# CarPreamp.net
KiCad netlist of a schematic drawn in EAGLE
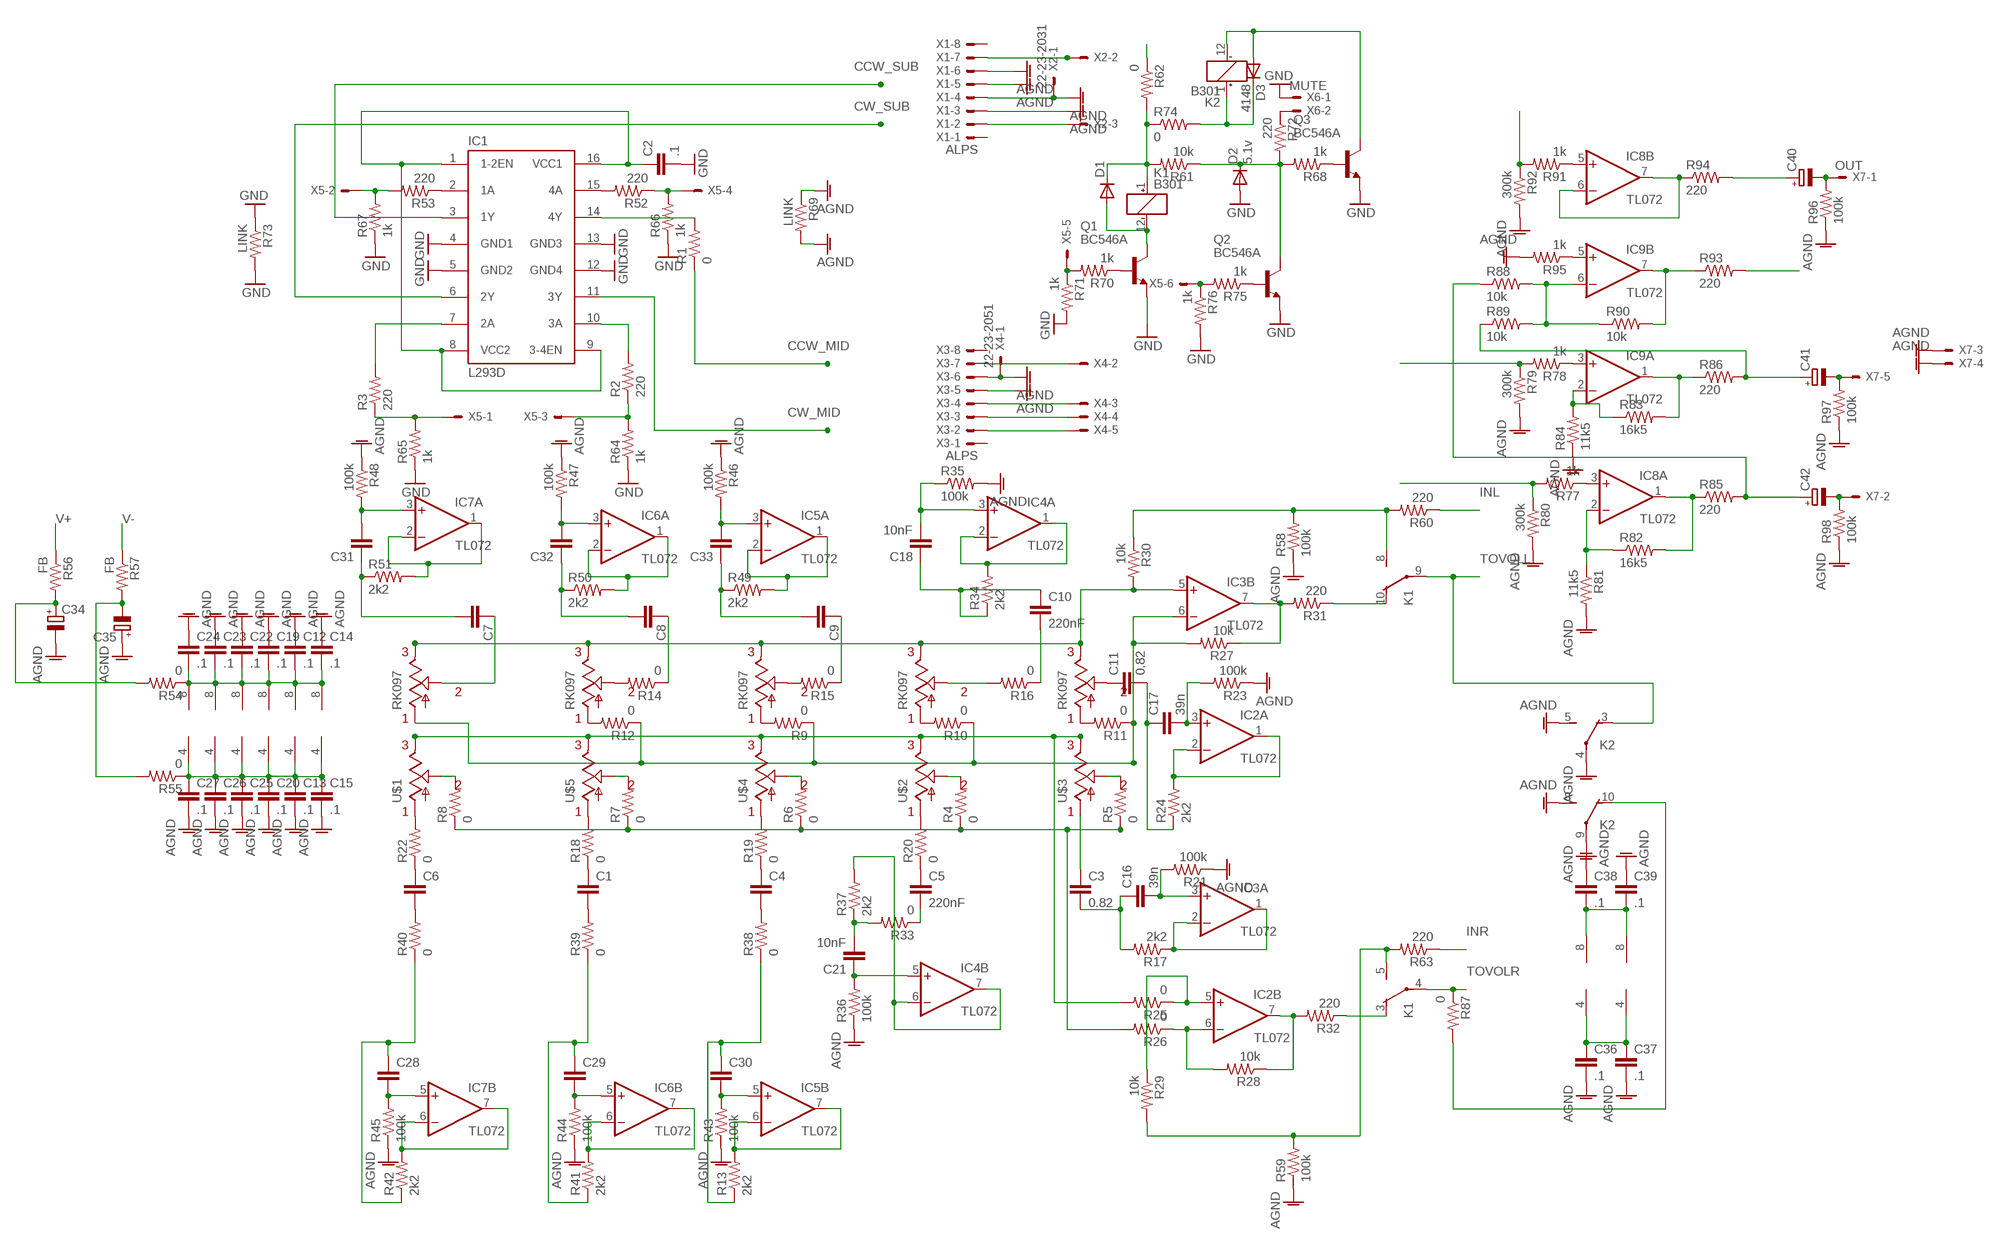
[diagram p0: schematic, sheet 1]

(export (version "E")
  (design (tool "Eeschema 10.0.6"))
  (components
    (comp (ref "C1")
      (value "C-EU050-035X075")
      (footprint "eagle-import:C050-035X075")
      (libsource (lib "eagle-import") (part "C-EU050-035X075"))
    )
    (comp (ref "C2")
      (value ".1")
      (footprint "eagle-import:C1210")
      (libsource (lib "eagle-import") (part "C-EUC1210"))
    )
    (comp (ref "C3")
      (value "0.82")
      (footprint "eagle-import:C075-032X103")
      (libsource (lib "eagle-import") (part "C-EU075-032X103"))
    )
    (comp (ref "C4")
      (value "C-EU050-035X075")
      (footprint "eagle-import:C050-035X075")
      (libsource (lib "eagle-import") (part "C-EU050-035X075"))
    )
    (comp (ref "C5")
      (value "220nF")
      (footprint "eagle-import:C050-035X075")
      (libsource (lib "eagle-import") (part "C-EU050-035X075"))
    )
    (comp (ref "C6")
      (value "C-EU050-035X075")
      (footprint "eagle-import:C050-035X075")
      (libsource (lib "eagle-import") (part "C-EU050-035X075"))
    )
    (comp (ref "C7")
      (value "C-EU050-035X075")
      (footprint "eagle-import:C050-035X075")
      (libsource (lib "eagle-import") (part "C-EU050-035X075"))
    )
    (comp (ref "C8")
      (value "C-EU050-035X075")
      (footprint "eagle-import:C050-035X075")
      (libsource (lib "eagle-import") (part "C-EU050-035X075"))
    )
    (comp (ref "C9")
      (value "C-EU050-035X075")
      (footprint "eagle-import:C050-035X075")
      (libsource (lib "eagle-import") (part "C-EU050-035X075"))
    )
    (comp (ref "C10")
      (value "220nF")
      (footprint "eagle-import:C050-035X075")
      (libsource (lib "eagle-import") (part "C-EU050-035X075"))
    )
    (comp (ref "C11")
      (value "0.82")
      (footprint "eagle-import:C075-032X103")
      (libsource (lib "eagle-import") (part "C-EU075-032X103"))
    )
    (comp (ref "C12")
      (value ".1")
      (footprint "eagle-import:C1210")
      (libsource (lib "eagle-import") (part "C-EUC1210"))
    )
    (comp (ref "C13")
      (value ".1")
      (footprint "eagle-import:C1210")
      (libsource (lib "eagle-import") (part "C-EUC1210"))
    )
    (comp (ref "C14")
      (value ".1")
      (footprint "eagle-import:C1210")
      (libsource (lib "eagle-import") (part "C-EUC1210"))
    )
    (comp (ref "C15")
      (value ".1")
      (footprint "eagle-import:C1210")
      (libsource (lib "eagle-import") (part "C-EUC1210"))
    )
    (comp (ref "C16")
      (value "39n")
      (footprint "eagle-import:C050-035X075")
      (libsource (lib "eagle-import") (part "C-EU050-035X075"))
    )
    (comp (ref "C17")
      (value "39n")
      (footprint "eagle-import:C050-035X075")
      (libsource (lib "eagle-import") (part "C-EU050-035X075"))
    )
    (comp (ref "C18")
      (value "10nF")
      (footprint "eagle-import:C050-035X075")
      (libsource (lib "eagle-import") (part "C-EU050-035X075"))
    )
    (comp (ref "C19")
      (value ".1")
      (footprint "eagle-import:C1210")
      (libsource (lib "eagle-import") (part "C-EUC1210"))
    )
    (comp (ref "C20")
      (value ".1")
      (footprint "eagle-import:C1210")
      (libsource (lib "eagle-import") (part "C-EUC1210"))
    )
    (comp (ref "C21")
      (value "10nF")
      (footprint "eagle-import:C050-035X075")
      (libsource (lib "eagle-import") (part "C-EU050-035X075"))
    )
    (comp (ref "C22")
      (value ".1")
      (footprint "eagle-import:C1210")
      (libsource (lib "eagle-import") (part "C-EUC1210"))
    )
    (comp (ref "C23")
      (value ".1")
      (footprint "eagle-import:C1210")
      (libsource (lib "eagle-import") (part "C-EUC1210"))
    )
    (comp (ref "C24")
      (value ".1")
      (footprint "eagle-import:C1210")
      (libsource (lib "eagle-import") (part "C-EUC1210"))
    )
    (comp (ref "C25")
      (value ".1")
      (footprint "eagle-import:C1210")
      (libsource (lib "eagle-import") (part "C-EUC1210"))
    )
    (comp (ref "C26")
      (value ".1")
      (footprint "eagle-import:C1210")
      (libsource (lib "eagle-import") (part "C-EUC1210"))
    )
    (comp (ref "C27")
      (value ".1")
      (footprint "eagle-import:C1210")
      (libsource (lib "eagle-import") (part "C-EUC1210"))
    )
    (comp (ref "C28")
      (value "C-EU050-035X075")
      (footprint "eagle-import:C050-035X075")
      (libsource (lib "eagle-import") (part "C-EU050-035X075"))
    )
    (comp (ref "C29")
      (value "C-EU050-035X075")
      (footprint "eagle-import:C050-035X075")
      (libsource (lib "eagle-import") (part "C-EU050-035X075"))
    )
    (comp (ref "C30")
      (value "C-EU050-035X075")
      (footprint "eagle-import:C050-035X075")
      (libsource (lib "eagle-import") (part "C-EU050-035X075"))
    )
    (comp (ref "C31")
      (value "C-EU050-035X075")
      (footprint "eagle-import:C050-035X075")
      (libsource (lib "eagle-import") (part "C-EU050-035X075"))
    )
    (comp (ref "C32")
      (value "C-EU050-035X075")
      (footprint "eagle-import:C050-035X075")
      (libsource (lib "eagle-import") (part "C-EU050-035X075"))
    )
    (comp (ref "C33")
      (value "C-EU050-035X075")
      (footprint "eagle-import:C050-035X075")
      (libsource (lib "eagle-import") (part "C-EU050-035X075"))
    )
    (comp (ref "C34")
      (value "CPOL-EUE3.5-8")
      (footprint "eagle-import:E3,5-8")
      (libsource (lib "eagle-import") (part "CPOL-EUE3.5-8"))
    )
    (comp (ref "C35")
      (value "CPOL-EUE3.5-8")
      (footprint "eagle-import:E3,5-8")
      (libsource (lib "eagle-import") (part "CPOL-EUE3.5-8"))
    )
    (comp (ref "C36")
      (value ".1")
      (footprint "eagle-import:C1210")
      (libsource (lib "eagle-import") (part "C-EUC1210"))
    )
    (comp (ref "C37")
      (value ".1")
      (footprint "eagle-import:C1210")
      (libsource (lib "eagle-import") (part "C-EUC1210"))
    )
    (comp (ref "C38")
      (value ".1")
      (footprint "eagle-import:C1210")
      (libsource (lib "eagle-import") (part "C-EUC1210"))
    )
    (comp (ref "C39")
      (value ".1")
      (footprint "eagle-import:C1210")
      (libsource (lib "eagle-import") (part "C-EUC1210"))
    )
    (comp (ref "C40")
      (value "CPOL-EUE3.5-8")
      (footprint "eagle-import:E3,5-8")
      (libsource (lib "eagle-import") (part "CPOL-EUE3.5-8"))
    )
    (comp (ref "C41")
      (value "CPOL-EUE3.5-8")
      (footprint "eagle-import:E3,5-8")
      (libsource (lib "eagle-import") (part "CPOL-EUE3.5-8"))
    )
    (comp (ref "C42")
      (value "CPOL-EUE3.5-8")
      (footprint "eagle-import:E3,5-8")
      (libsource (lib "eagle-import") (part "CPOL-EUE3.5-8"))
    )
    (comp (ref "D1")
      (value "1N4148DO35-10")
      (footprint "eagle-import:DO35-10")
      (libsource (lib "eagle-import") (part "1N4148DO35-10"))
    )
    (comp (ref "D2")
      (value "5.1v")
      (footprint "eagle-import:DO35-10")
      (libsource (lib "eagle-import") (part "1N4148DO35-10"))
    )
    (comp (ref "D3")
      (value "4148")
      (footprint "eagle-import:DO35-10")
      (libsource (lib "eagle-import") (part "1N4148DO35-10"))
    )
    (comp (ref "IC1")
      (value "L293D")
      (footprint "eagle-import:DIL16")
      (libsource (lib "eagle-import") (part "L293D"))
    )
    (comp (ref "IC2")
      (value "TL072")
      (footprint "eagle-import:DIL08")
      (libsource (lib "eagle-import") (part "1458NLM"))
    )
    (comp (ref "IC3")
      (value "TL072")
      (footprint "eagle-import:DIL08")
      (libsource (lib "eagle-import") (part "1458NLM"))
    )
    (comp (ref "IC4")
      (value "TL072")
      (footprint "eagle-import:DIL08")
      (libsource (lib "eagle-import") (part "1458NLM"))
    )
    (comp (ref "IC5")
      (value "TL072")
      (footprint "eagle-import:DIL08")
      (libsource (lib "eagle-import") (part "1458NLM"))
    )
    (comp (ref "IC6")
      (value "TL072")
      (footprint "eagle-import:DIL08")
      (libsource (lib "eagle-import") (part "1458NLM"))
    )
    (comp (ref "IC7")
      (value "TL072")
      (footprint "eagle-import:DIL08")
      (libsource (lib "eagle-import") (part "1458NLM"))
    )
    (comp (ref "IC8")
      (value "TL072")
      (footprint "eagle-import:DIL08")
      (libsource (lib "eagle-import") (part "1458NLM"))
    )
    (comp (ref "IC9")
      (value "TL072")
      (footprint "eagle-import:DIL08")
      (libsource (lib "eagle-import") (part "1458NLM"))
    )
    (comp (ref "K1")
      (value "B301")
      (footprint "eagle-import:TXD2")
      (libsource (lib "eagle-import") (part "TX?-D26V"))
    )
    (comp (ref "K2")
      (value "B301")
      (footprint "eagle-import:TXD2")
      (libsource (lib "eagle-import") (part "TX?-D26V"))
    )
    (comp (ref "Q1")
      (value "BC546A")
      (footprint "eagle-import:TO92-EBC")
      (libsource (lib "eagle-import") (part "BC546A"))
    )
    (comp (ref "Q2")
      (value "BC546A")
      (footprint "eagle-import:TO92-EBC")
      (libsource (lib "eagle-import") (part "BC546A"))
    )
    (comp (ref "Q3")
      (value "BC546A")
      (footprint "eagle-import:TO92-EBC")
      (libsource (lib "eagle-import") (part "BC546A"))
    )
    (comp (ref "R1")
      (value "0")
      (footprint "eagle-import:0309_12")
      (libsource (lib "eagle-import") (part "R-US_0309/12"))
    )
    (comp (ref "R2")
      (value "220")
      (footprint "eagle-import:0309_12")
      (libsource (lib "eagle-import") (part "R-US_0309/12"))
    )
    (comp (ref "R3")
      (value "220")
      (footprint "eagle-import:0207_15")
      (libsource (lib "eagle-import") (part "R-US_0207/15"))
    )
    (comp (ref "R4")
      (value "0")
      (footprint "eagle-import:0207_7")
      (libsource (lib "eagle-import") (part "R-US_0207/7"))
    )
    (comp (ref "R5")
      (value "0")
      (footprint "eagle-import:0207_7")
      (libsource (lib "eagle-import") (part "R-US_0207/7"))
    )
    (comp (ref "R6")
      (value "0")
      (footprint "eagle-import:0207_7")
      (libsource (lib "eagle-import") (part "R-US_0207/7"))
    )
    (comp (ref "R7")
      (value "0")
      (footprint "eagle-import:0207_7")
      (libsource (lib "eagle-import") (part "R-US_0207/7"))
    )
    (comp (ref "R8")
      (value "0")
      (footprint "eagle-import:0207_7")
      (libsource (lib "eagle-import") (part "R-US_0207/7"))
    )
    (comp (ref "R9")
      (value "0")
      (footprint "eagle-import:0207_7")
      (libsource (lib "eagle-import") (part "R-US_0207/7"))
    )
    (comp (ref "R10")
      (value "0")
      (footprint "eagle-import:0207_7")
      (libsource (lib "eagle-import") (part "R-US_0207/7"))
    )
    (comp (ref "R11")
      (value "0")
      (footprint "eagle-import:0207_7")
      (libsource (lib "eagle-import") (part "R-US_0207/7"))
    )
    (comp (ref "R12")
      (value "0")
      (footprint "eagle-import:0207_7")
      (libsource (lib "eagle-import") (part "R-US_0207/7"))
    )
    (comp (ref "R13")
      (value "2k2")
      (footprint "eagle-import:0207_7")
      (libsource (lib "eagle-import") (part "R-US_0207/7"))
    )
    (comp (ref "R14")
      (value "0")
      (footprint "eagle-import:0207_7")
      (libsource (lib "eagle-import") (part "R-US_0207/7"))
    )
    (comp (ref "R15")
      (value "0")
      (footprint "eagle-import:0207_7")
      (libsource (lib "eagle-import") (part "R-US_0207/7"))
    )
    (comp (ref "R16")
      (value "0")
      (footprint "eagle-import:0207_7")
      (libsource (lib "eagle-import") (part "R-US_0207/7"))
    )
    (comp (ref "R17")
      (value "2k2")
      (footprint "eagle-import:0207_7")
      (libsource (lib "eagle-import") (part "R-US_0207/7"))
    )
    (comp (ref "R18")
      (value "0")
      (footprint "eagle-import:0207_7")
      (libsource (lib "eagle-import") (part "R-US_0207/7"))
    )
    (comp (ref "R19")
      (value "0")
      (footprint "eagle-import:0207_7")
      (libsource (lib "eagle-import") (part "R-US_0207/7"))
    )
    (comp (ref "R20")
      (value "0")
      (footprint "eagle-import:0207_7")
      (libsource (lib "eagle-import") (part "R-US_0207/7"))
    )
    (comp (ref "R21")
      (value "100k")
      (footprint "eagle-import:0207_7")
      (libsource (lib "eagle-import") (part "R-US_0207/7"))
    )
    (comp (ref "R22")
      (value "0")
      (footprint "eagle-import:0207_7")
      (libsource (lib "eagle-import") (part "R-US_0207/7"))
    )
    (comp (ref "R23")
      (value "100k")
      (footprint "eagle-import:0207_7")
      (libsource (lib "eagle-import") (part "R-US_0207/7"))
    )
    (comp (ref "R24")
      (value "2k2")
      (footprint "eagle-import:0207_7")
      (libsource (lib "eagle-import") (part "R-US_0207/7"))
    )
    (comp (ref "R25")
      (value "0")
      (footprint "eagle-import:0207_10")
      (libsource (lib "eagle-import") (part "R-US_0207/10"))
    )
    (comp (ref "R26")
      (value "0")
      (footprint "eagle-import:0207_12")
      (libsource (lib "eagle-import") (part "R-US_0207/12"))
    )
    (comp (ref "R27")
      (value "10k")
      (footprint "eagle-import:R1210")
      (libsource (lib "eagle-import") (part "R-US_R1210"))
    )
    (comp (ref "R28")
      (value "10k")
      (footprint "eagle-import:R1210")
      (libsource (lib "eagle-import") (part "R-US_R1210"))
    )
    (comp (ref "R29")
      (value "10k")
      (footprint "eagle-import:0207_7")
      (libsource (lib "eagle-import") (part "R-US_0207/7"))
    )
    (comp (ref "R30")
      (value "10k")
      (footprint "eagle-import:0207_12")
      (libsource (lib "eagle-import") (part "R-US_0207/12"))
    )
    (comp (ref "R31")
      (value "220")
      (footprint "eagle-import:0207_7")
      (libsource (lib "eagle-import") (part "R-US_0207/7"))
    )
    (comp (ref "R32")
      (value "220")
      (footprint "eagle-import:0207_12")
      (libsource (lib "eagle-import") (part "R-US_0207/12"))
    )
    (comp (ref "R33")
      (value "0")
      (footprint "eagle-import:0309_10")
      (libsource (lib "eagle-import") (part "R-US_0309/10"))
    )
    (comp (ref "R34")
      (value "2k2")
      (footprint "eagle-import:0207_7")
      (libsource (lib "eagle-import") (part "R-US_0207/7"))
    )
    (comp (ref "R35")
      (value "100k")
      (footprint "eagle-import:0207_7")
      (libsource (lib "eagle-import") (part "R-US_0207/7"))
    )
    (comp (ref "R36")
      (value "100k")
      (footprint "eagle-import:0207_7")
      (libsource (lib "eagle-import") (part "R-US_0207/7"))
    )
    (comp (ref "R37")
      (value "2k2")
      (footprint "eagle-import:0207_7")
      (libsource (lib "eagle-import") (part "R-US_0207/7"))
    )
    (comp (ref "R38")
      (value "0")
      (footprint "eagle-import:0207_10")
      (libsource (lib "eagle-import") (part "R-US_0207/10"))
    )
    (comp (ref "R39")
      (value "0")
      (footprint "eagle-import:0207_10")
      (libsource (lib "eagle-import") (part "R-US_0207/10"))
    )
    (comp (ref "R40")
      (value "0")
      (footprint "eagle-import:0207_10")
      (libsource (lib "eagle-import") (part "R-US_0207/10"))
    )
    (comp (ref "R41")
      (value "2k2")
      (footprint "eagle-import:0207_7")
      (libsource (lib "eagle-import") (part "R-US_0207/7"))
    )
    (comp (ref "R42")
      (value "2k2")
      (footprint "eagle-import:0207_7")
      (libsource (lib "eagle-import") (part "R-US_0207/7"))
    )
    (comp (ref "R43")
      (value "100k")
      (footprint "eagle-import:0207_7")
      (libsource (lib "eagle-import") (part "R-US_0207/7"))
    )
    (comp (ref "R44")
      (value "100k")
      (footprint "eagle-import:0207_7")
      (libsource (lib "eagle-import") (part "R-US_0207/7"))
    )
    (comp (ref "R45")
      (value "100k")
      (footprint "eagle-import:0207_7")
      (libsource (lib "eagle-import") (part "R-US_0207/7"))
    )
    (comp (ref "R46")
      (value "100k")
      (footprint "eagle-import:0207_7")
      (libsource (lib "eagle-import") (part "R-US_0207/7"))
    )
    (comp (ref "R47")
      (value "100k")
      (footprint "eagle-import:0207_7")
      (libsource (lib "eagle-import") (part "R-US_0207/7"))
    )
    (comp (ref "R48")
      (value "100k")
      (footprint "eagle-import:0207_7")
      (libsource (lib "eagle-import") (part "R-US_0207/7"))
    )
    (comp (ref "R49")
      (value "2k2")
      (footprint "eagle-import:0207_7")
      (libsource (lib "eagle-import") (part "R-US_0207/7"))
    )
    (comp (ref "R50")
      (value "2k2")
      (footprint "eagle-import:0207_7")
      (libsource (lib "eagle-import") (part "R-US_0207/7"))
    )
    (comp (ref "R51")
      (value "2k2")
      (footprint "eagle-import:0207_7")
      (libsource (lib "eagle-import") (part "R-US_0207/7"))
    )
    (comp (ref "R52")
      (value "220")
      (footprint "eagle-import:0309_10")
      (libsource (lib "eagle-import") (part "R-US_0309/10"))
    )
    (comp (ref "R53")
      (value "220")
      (footprint "eagle-import:0309_10")
      (libsource (lib "eagle-import") (part "R-US_0309/10"))
    )
    (comp (ref "R54")
      (value "0")
      (footprint "eagle-import:0309_10")
      (libsource (lib "eagle-import") (part "R-US_0309/10"))
    )
    (comp (ref "R55")
      (value "0")
      (footprint "eagle-import:0411_15")
      (libsource (lib "eagle-import") (part "R-US_0411/15"))
    )
    (comp (ref "R56")
      (value "FB")
      (footprint "eagle-import:0309_12")
      (libsource (lib "eagle-import") (part "R-US_0309/12"))
    )
    (comp (ref "R57")
      (value "FB")
      (footprint "eagle-import:0309_12")
      (libsource (lib "eagle-import") (part "R-US_0309/12"))
    )
    (comp (ref "R58")
      (value "100k")
      (footprint "eagle-import:0207_7")
      (libsource (lib "eagle-import") (part "R-US_0207/7"))
    )
    (comp (ref "R59")
      (value "100k")
      (footprint "eagle-import:0207_7")
      (libsource (lib "eagle-import") (part "R-US_0207/7"))
    )
    (comp (ref "R60")
      (value "220")
      (footprint "eagle-import:0207_7")
      (libsource (lib "eagle-import") (part "R-US_0207/7"))
    )
    (comp (ref "R61")
      (value "10k")
      (footprint "eagle-import:R1210")
      (libsource (lib "eagle-import") (part "R-US_R1210"))
    )
    (comp (ref "R62")
      (value "0")
      (footprint "eagle-import:0309_10")
      (libsource (lib "eagle-import") (part "R-US_0309/10"))
    )
    (comp (ref "R63")
      (value "220")
      (footprint "eagle-import:0207_7")
      (libsource (lib "eagle-import") (part "R-US_0207/7"))
    )
    (comp (ref "R64")
      (value "1k")
      (footprint "eagle-import:R1210")
      (libsource (lib "eagle-import") (part "R-US_R1210"))
    )
    (comp (ref "R65")
      (value "1k")
      (footprint "eagle-import:R1210")
      (libsource (lib "eagle-import") (part "R-US_R1210"))
    )
    (comp (ref "R66")
      (value "1k")
      (footprint "eagle-import:R1210")
      (libsource (lib "eagle-import") (part "R-US_R1210"))
    )
    (comp (ref "R67")
      (value "1k")
      (footprint "eagle-import:R1210")
      (libsource (lib "eagle-import") (part "R-US_R1210"))
    )
    (comp (ref "R68")
      (value "1k")
      (footprint "eagle-import:R1210")
      (libsource (lib "eagle-import") (part "R-US_R1210"))
    )
    (comp (ref "R69")
      (value "LINK")
      (footprint "eagle-import:0309_12")
      (libsource (lib "eagle-import") (part "R-US_0309/12"))
    )
    (comp (ref "R70")
      (value "1k")
      (footprint "eagle-import:R1210")
      (libsource (lib "eagle-import") (part "R-US_R1210"))
    )
    (comp (ref "R71")
      (value "1k")
      (footprint "eagle-import:R1210")
      (libsource (lib "eagle-import") (part "R-US_R1210"))
    )
    (comp (ref "R72")
      (value "220")
      (footprint "eagle-import:R1210")
      (libsource (lib "eagle-import") (part "R-US_R1210"))
    )
    (comp (ref "R73")
      (value "LINK")
      (footprint "eagle-import:0309_10")
      (libsource (lib "eagle-import") (part "R-US_0309/10"))
    )
    (comp (ref "R74")
      (value "0")
      (footprint "eagle-import:0309_12")
      (libsource (lib "eagle-import") (part "R-US_0309/12"))
    )
    (comp (ref "R75")
      (value "1k")
      (footprint "eagle-import:0309_10")
      (libsource (lib "eagle-import") (part "R-US_0309/10"))
    )
    (comp (ref "R76")
      (value "1k")
      (footprint "eagle-import:0309_10")
      (libsource (lib "eagle-import") (part "R-US_0309/10"))
    )
    (comp (ref "R77")
      (value "1k")
      (footprint "eagle-import:0207_7")
      (libsource (lib "eagle-import") (part "R-US_0207/7"))
    )
    (comp (ref "R78")
      (value "1k")
      (footprint "eagle-import:0207_7")
      (libsource (lib "eagle-import") (part "R-US_0207/7"))
    )
    (comp (ref "R79")
      (value "300k")
      (footprint "eagle-import:0207_7")
      (libsource (lib "eagle-import") (part "R-US_0207/7"))
    )
    (comp (ref "R80")
      (value "300k")
      (footprint "eagle-import:0207_7")
      (libsource (lib "eagle-import") (part "R-US_0207/7"))
    )
    (comp (ref "R81")
      (value "11k5")
      (footprint "eagle-import:0207_7")
      (libsource (lib "eagle-import") (part "R-US_0207/7"))
    )
    (comp (ref "R82")
      (value "16k5")
      (footprint "eagle-import:0207_7")
      (libsource (lib "eagle-import") (part "R-US_0207/7"))
    )
    (comp (ref "R83")
      (value "16k5")
      (footprint "eagle-import:0207_7")
      (libsource (lib "eagle-import") (part "R-US_0207/7"))
    )
    (comp (ref "R84")
      (value "11k5")
      (footprint "eagle-import:0207_7")
      (libsource (lib "eagle-import") (part "R-US_0207/7"))
    )
    (comp (ref "R85")
      (value "220")
      (footprint "eagle-import:0207_7")
      (libsource (lib "eagle-import") (part "R-US_0207/7"))
    )
    (comp (ref "R86")
      (value "220")
      (footprint "eagle-import:0207_7")
      (libsource (lib "eagle-import") (part "R-US_0207/7"))
    )
    (comp (ref "R87")
      (value "0")
      (footprint "eagle-import:0207_10")
      (libsource (lib "eagle-import") (part "R-US_0207/10"))
    )
    (comp (ref "R88")
      (value "10k")
      (footprint "eagle-import:0207_7")
      (libsource (lib "eagle-import") (part "R-US_0207/7"))
    )
    (comp (ref "R89")
      (value "10k")
      (footprint "eagle-import:0207_7")
      (libsource (lib "eagle-import") (part "R-US_0207/7"))
    )
    (comp (ref "R90")
      (value "10k")
      (footprint "eagle-import:0207_7")
      (libsource (lib "eagle-import") (part "R-US_0207/7"))
    )
    (comp (ref "R91")
      (value "1k")
      (footprint "eagle-import:0207_7")
      (libsource (lib "eagle-import") (part "R-US_0207/7"))
    )
    (comp (ref "R92")
      (value "300k")
      (footprint "eagle-import:0207_7")
      (libsource (lib "eagle-import") (part "R-US_0207/7"))
    )
    (comp (ref "R93")
      (value "220")
      (footprint "eagle-import:0207_7")
      (libsource (lib "eagle-import") (part "R-US_0207/7"))
    )
    (comp (ref "R94")
      (value "220")
      (footprint "eagle-import:0207_7")
      (libsource (lib "eagle-import") (part "R-US_0207/7"))
    )
    (comp (ref "R95")
      (value "1k")
      (footprint "eagle-import:0207_10")
      (libsource (lib "eagle-import") (part "R-US_0207/10"))
    )
    (comp (ref "R96")
      (value "100k")
      (footprint "eagle-import:0207_7")
      (libsource (lib "eagle-import") (part "R-US_0207/7"))
    )
    (comp (ref "R97")
      (value "100k")
      (footprint "eagle-import:0207_7")
      (libsource (lib "eagle-import") (part "R-US_0207/7"))
    )
    (comp (ref "R98")
      (value "100k")
      (footprint "eagle-import:0207_7")
      (libsource (lib "eagle-import") (part "R-US_0207/7"))
    )
    (comp (ref "U$1")
      (value "RK097")
      (footprint "eagle-import:RK097-DUAL-ELEMENT")
      (libsource (lib "eagle-import") (part "RK097-DUAL-ELEMENT"))
    )
    (comp (ref "U$2")
      (value "RK097")
      (footprint "eagle-import:RK097-DUAL-ELEMENT")
      (libsource (lib "eagle-import") (part "RK097-DUAL-ELEMENT"))
    )
    (comp (ref "U$3")
      (value "RK097")
      (footprint "eagle-import:RK097-DUAL-ELEMENT")
      (libsource (lib "eagle-import") (part "RK097-DUAL-ELEMENT"))
    )
    (comp (ref "U$4")
      (value "RK097")
      (footprint "eagle-import:RK097-DUAL-ELEMENT")
      (libsource (lib "eagle-import") (part "RK097-DUAL-ELEMENT"))
    )
    (comp (ref "U$5")
      (value "RK097")
      (footprint "eagle-import:RK097-DUAL-ELEMENT")
      (libsource (lib "eagle-import") (part "RK097-DUAL-ELEMENT"))
    )
    (comp (ref "X1")
      (value "ALPS")
      (footprint "eagle-import:22-23-2081")
      (fields (field (name "MF") "MOLEX") (field (name "MPN") "22-23-2081"))
      (libsource (lib "eagle-import") (part "22-23-2081"))
    )
    (comp (ref "X2")
      (value "22-23-2031")
      (footprint "eagle-import:22-23-2031")
      (fields (field (name "MF") "MOLEX"))
      (libsource (lib "eagle-import") (part "22-23-2031"))
    )
    (comp (ref "X3")
      (value "ALPS")
      (footprint "eagle-import:22-23-2081")
      (fields (field (name "MF") "MOLEX") (field (name "MPN") "22-23-2081"))
      (libsource (lib "eagle-import") (part "22-23-2081"))
    )
    (comp (ref "X4")
      (value "22-23-2051")
      (footprint "eagle-import:22-23-2051")
      (fields (field (name "MF") "MOLEX"))
      (libsource (lib "eagle-import") (part "22-23-2051"))
    )
    (comp (ref "X5")
      (value "22-23-2061")
      (footprint "eagle-import:22-23-2061")
      (fields (field (name "MF") "MOLEX"))
      (libsource (lib "eagle-import") (part "22-23-2061"))
    )
    (comp (ref "X6")
      (value "MUTE")
      (footprint "eagle-import:22-23-2021")
      (fields (field (name "MF") "MOLEX") (field (name "MPN") "22-23-2021"))
      (libsource (lib "eagle-import") (part "22-23-2021"))
    )
    (comp (ref "X7")
      (value "OUT")
      (footprint "eagle-import:22-23-2051")
      (fields (field (name "MF") "MOLEX") (field (name "MPN") "22-23-2051"))
      (libsource (lib "eagle-import") (part "22-23-2051"))
    )
  )
  (nets
    (net (code "1") (name "/5V") (class "Default")
      (node (ref "C2") (pin "1") (pinfunction "1_1") (pintype "passive"))
      (node (ref "IC1") (pin "1") (pinfunction "1-2EN_1") (pintype "input"))
      (node (ref "IC1") (pin "16") (pinfunction "VCC1_16") (pintype "power_in"))
      (node (ref "IC1") (pin "8") (pinfunction "VCC2_8") (pintype "power_in"))
      (node (ref "IC1") (pin "9") (pinfunction "3-4EN_9") (pintype "input"))
      (node (ref "R62") (pin "1") (pinfunction "1_1") (pintype "passive"))
    )
    (net (code "2") (name "/CCW_MID") (class "Default")
      (node (ref "R1") (pin "1") (pinfunction "1_1") (pintype "passive"))
    )
    (net (code "3") (name "/CCW_SUB") (class "Default")
      (node (ref "IC1") (pin "3") (pinfunction "1Y_3") (pintype "output"))
    )
    (net (code "4") (name "/CW_MID") (class "Default")
      (node (ref "IC1") (pin "11") (pinfunction "3Y_11") (pintype "output"))
    )
    (net (code "5") (name "/CW_SUB") (class "Default")
      (node (ref "IC1") (pin "6") (pinfunction "2Y_6") (pintype "output"))
    )
    (net (code "6") (name "/INL") (class "Default")
      (node (ref "R60") (pin "1") (pinfunction "1_1") (pintype "passive"))
    )
    (net (code "7") (name "/INR") (class "Default")
      (node (ref "R63") (pin "1") (pinfunction "1_1") (pintype "passive"))
    )
    (net (code "8") (name "/TOVOLL") (class "Default")
      (node (ref "K1") (pin "9") (pinfunction "P_9") (pintype "passive"))
      (node (ref "K2") (pin "3") (pinfunction "O_3") (pintype "passive"))
    )
    (net (code "9") (name "/TOVOLR") (class "Default")
      (node (ref "K1") (pin "4") (pinfunction "P_4") (pintype "passive"))
      (node (ref "R87") (pin "1") (pinfunction "1_1") (pintype "passive"))
    )
    (net (code "10") (name "/V+") (class "Default")
      (node (ref "R56") (pin "1") (pinfunction "1_1") (pintype "passive"))
    )
    (net (code "11") (name "/V-") (class "Default")
      (node (ref "R57") (pin "1") (pinfunction "1_1") (pintype "passive"))
    )
    (net (code "12") (name "AGND") (class "Default")
      (node (ref "C12") (pin "1") (pinfunction "1_1") (pintype "passive"))
      (node (ref "C13") (pin "2") (pinfunction "2_2") (pintype "passive"))
      (node (ref "C14") (pin "1") (pinfunction "1_1") (pintype "passive"))
      (node (ref "C15") (pin "2") (pinfunction "2_2") (pintype "passive"))
      (node (ref "C19") (pin "1") (pinfunction "1_1") (pintype "passive"))
      (node (ref "C20") (pin "2") (pinfunction "2_2") (pintype "passive"))
      (node (ref "C22") (pin "1") (pinfunction "1_1") (pintype "passive"))
      (node (ref "C23") (pin "1") (pinfunction "1_1") (pintype "passive"))
      (node (ref "C24") (pin "1") (pinfunction "1_1") (pintype "passive"))
      (node (ref "C25") (pin "2") (pinfunction "2_2") (pintype "passive"))
      (node (ref "C26") (pin "2") (pinfunction "2_2") (pintype "passive"))
      (node (ref "C27") (pin "2") (pinfunction "2_2") (pintype "passive"))
      (node (ref "C34") (pin "-") (pinfunction "-_-") (pintype "passive"))
      (node (ref "C35") (pin "+") (pinfunction "+_+") (pintype "passive"))
      (node (ref "C36") (pin "2") (pinfunction "2_2") (pintype "passive"))
      (node (ref "C37") (pin "2") (pinfunction "2_2") (pintype "passive"))
      (node (ref "C38") (pin "1") (pinfunction "1_1") (pintype "passive"))
      (node (ref "C39") (pin "1") (pinfunction "1_1") (pintype "passive"))
      (node (ref "K2") (pin "4") (pinfunction "P_4") (pintype "passive"))
      (node (ref "K2") (pin "5") (pinfunction "S_5") (pintype "passive"))
      (node (ref "K2") (pin "8") (pinfunction "S_8") (pintype "passive"))
      (node (ref "K2") (pin "9") (pinfunction "P_9") (pintype "passive"))
      (node (ref "R21") (pin "1") (pinfunction "1_1") (pintype "passive"))
      (node (ref "R23") (pin "1") (pinfunction "1_1") (pintype "passive"))
      (node (ref "R35") (pin "2") (pinfunction "2_2") (pintype "passive"))
      (node (ref "R36") (pin "1") (pinfunction "1_1") (pintype "passive"))
      (node (ref "R43") (pin "1") (pinfunction "1_1") (pintype "passive"))
      (node (ref "R44") (pin "1") (pinfunction "1_1") (pintype "passive"))
      (node (ref "R45") (pin "1") (pinfunction "1_1") (pintype "passive"))
      (node (ref "R46") (pin "1") (pinfunction "1_1") (pintype "passive"))
      (node (ref "R47") (pin "1") (pinfunction "1_1") (pintype "passive"))
      (node (ref "R48") (pin "1") (pinfunction "1_1") (pintype "passive"))
      (node (ref "R58") (pin "1") (pinfunction "1_1") (pintype "passive"))
      (node (ref "R59") (pin "1") (pinfunction "1_1") (pintype "passive"))
      (node (ref "R69") (pin "1") (pinfunction "1_1") (pintype "passive"))
      (node (ref "R69") (pin "2") (pinfunction "2_2") (pintype "passive"))
      (node (ref "R79") (pin "2") (pinfunction "2_2") (pintype "passive"))
      (node (ref "R80") (pin "2") (pinfunction "2_2") (pintype "passive"))
      (node (ref "R81") (pin "2") (pinfunction "2_2") (pintype "passive"))
      (node (ref "R84") (pin "1") (pinfunction "1_1") (pintype "passive"))
      (node (ref "R92") (pin "2") (pinfunction "2_2") (pintype "passive"))
      (node (ref "R95") (pin "2") (pinfunction "2_2") (pintype "passive"))
      (node (ref "R96") (pin "1") (pinfunction "1_1") (pintype "passive"))
      (node (ref "R97") (pin "1") (pinfunction "1_1") (pintype "passive"))
      (node (ref "R98") (pin "1") (pinfunction "1_1") (pintype "passive"))
      (node (ref "X1") (pin "3") (pinfunction "S_3") (pintype "passive"))
      (node (ref "X1") (pin "4") (pinfunction "S_4") (pintype "passive"))
      (node (ref "X1") (pin "5") (pinfunction "S_5") (pintype "passive"))
      (node (ref "X1") (pin "6") (pinfunction "S_6") (pintype "passive"))
      (node (ref "X2") (pin "1") (pinfunction "S_1") (pintype "passive"))
      (node (ref "X3") (pin "5") (pinfunction "S_5") (pintype "passive"))
      (node (ref "X3") (pin "6") (pinfunction "S_6") (pintype "passive"))
      (node (ref "X4") (pin "1") (pinfunction "S_1") (pintype "passive"))
      (node (ref "X7") (pin "3") (pinfunction "S_3") (pintype "passive"))
      (node (ref "X7") (pin "4") (pinfunction "S_4") (pintype "passive"))
    )
    (net (code "13") (name "GND") (class "Default")
      (node (ref "C2") (pin "2") (pinfunction "2_2") (pintype "passive"))
      (node (ref "D2") (pin "A") (pinfunction "A_A") (pintype "passive"))
      (node (ref "IC1") (pin "12") (pinfunction "GND4_12") (pintype "power_in"))
      (node (ref "IC1") (pin "13") (pinfunction "GND3_13") (pintype "power_in"))
      (node (ref "IC1") (pin "4") (pinfunction "GND1_4") (pintype "power_in"))
      (node (ref "IC1") (pin "5") (pinfunction "GND2_5") (pintype "power_in"))
      (node (ref "Q1") (pin "E") (pinfunction "E_E") (pintype "passive"))
      (node (ref "Q2") (pin "E") (pinfunction "E_E") (pintype "passive"))
      (node (ref "Q3") (pin "E") (pinfunction "E_E") (pintype "passive"))
      (node (ref "R64") (pin "1") (pinfunction "1_1") (pintype "passive"))
      (node (ref "R65") (pin "1") (pinfunction "1_1") (pintype "passive"))
      (node (ref "R66") (pin "1") (pinfunction "1_1") (pintype "passive"))
      (node (ref "R67") (pin "1") (pinfunction "1_1") (pintype "passive"))
      (node (ref "R71") (pin "2") (pinfunction "2_2") (pintype "passive"))
      (node (ref "R73") (pin "1") (pinfunction "1_1") (pintype "passive"))
      (node (ref "R73") (pin "2") (pinfunction "2_2") (pintype "passive"))
      (node (ref "R76") (pin "2") (pinfunction "2_2") (pintype "passive"))
      (node (ref "X6") (pin "1") (pinfunction "S_1") (pintype "passive"))
    )
    (net (code "14") (name "Net-(C1-Pad1)") (class "Default")
      (node (ref "C1") (pin "1") (pinfunction "1_1") (pintype "passive"))
      (node (ref "R18") (pin "1") (pinfunction "1_1") (pintype "passive"))
    )
    (net (code "15") (name "Net-(C1-Pad2)") (class "Default")
      (node (ref "C1") (pin "2") (pinfunction "2_2") (pintype "passive"))
      (node (ref "R39") (pin "2") (pinfunction "2_2") (pintype "passive"))
    )
    (net (code "16") (name "Net-(C4-Pad1)") (class "Default")
      (node (ref "C4") (pin "1") (pinfunction "1_1") (pintype "passive"))
      (node (ref "R19") (pin "1") (pinfunction "1_1") (pintype "passive"))
    )
    (net (code "17") (name "Net-(C4-Pad2)") (class "Default")
      (node (ref "C4") (pin "2") (pinfunction "2_2") (pintype "passive"))
      (node (ref "R38") (pin "2") (pinfunction "2_2") (pintype "passive"))
    )
    (net (code "18") (name "Net-(C5-Pad1)") (class "Default")
      (node (ref "C5") (pin "1") (pinfunction "1_1") (pintype "passive"))
      (node (ref "R20") (pin "1") (pinfunction "1_1") (pintype "passive"))
    )
    (net (code "19") (name "Net-(C5-Pad2)") (class "Default")
      (node (ref "C5") (pin "2") (pinfunction "2_2") (pintype "passive"))
      (node (ref "R33") (pin "1") (pinfunction "1_1") (pintype "passive"))
    )
    (net (code "20") (name "Net-(C6-Pad1)") (class "Default")
      (node (ref "C6") (pin "1") (pinfunction "1_1") (pintype "passive"))
      (node (ref "R22") (pin "1") (pinfunction "1_1") (pintype "passive"))
    )
    (net (code "21") (name "Net-(C6-Pad2)") (class "Default")
      (node (ref "C6") (pin "2") (pinfunction "2_2") (pintype "passive"))
      (node (ref "R40") (pin "2") (pinfunction "2_2") (pintype "passive"))
    )
    (net (code "22") (name "Net-(C8-Pad1)") (class "Default")
      (node (ref "C8") (pin "1") (pinfunction "1_1") (pintype "passive"))
      (node (ref "R14") (pin "1") (pinfunction "1_1") (pintype "passive"))
    )
    (net (code "23") (name "Net-(C9-Pad1)") (class "Default")
      (node (ref "C9") (pin "1") (pinfunction "1_1") (pintype "passive"))
      (node (ref "R15") (pin "1") (pinfunction "1_1") (pintype "passive"))
    )
    (net (code "24") (name "Net-(C10-Pad1)") (class "Default")
      (node (ref "C10") (pin "1") (pinfunction "1_1") (pintype "passive"))
      (node (ref "C18") (pin "1") (pinfunction "1_1") (pintype "passive"))
      (node (ref "R34") (pin "1") (pinfunction "1_1") (pintype "passive"))
    )
    (net (code "25") (name "Net-(C10-Pad2)") (class "Default")
      (node (ref "C10") (pin "2") (pinfunction "2_2") (pintype "passive"))
      (node (ref "R16") (pin "1") (pinfunction "1_1") (pintype "passive"))
    )
    (net (code "26") (name "Net-(C11-Pad2)") (class "Default")
      (node (ref "C11") (pin "2") (pinfunction "2_2") (pintype "passive"))
      (node (ref "C17") (pin "1") (pinfunction "1_1") (pintype "passive"))
      (node (ref "R24") (pin "1") (pinfunction "1_1") (pintype "passive"))
    )
    (net (code "27") (name "Net-(C16-Pad1)") (class "Default")
      (node (ref "C16") (pin "1") (pinfunction "1_1") (pintype "passive"))
      (node (ref "C3") (pin "2") (pinfunction "2_2") (pintype "passive"))
      (node (ref "R17") (pin "2") (pinfunction "2_2") (pintype "passive"))
    )
    (net (code "28") (name "Net-(C21-Pad2)") (class "Default")
      (node (ref "C21") (pin "2") (pinfunction "2_2") (pintype "passive"))
      (node (ref "R33") (pin "2") (pinfunction "2_2") (pintype "passive"))
      (node (ref "R37") (pin "1") (pinfunction "1_1") (pintype "passive"))
    )
    (net (code "29") (name "Net-(C28-Pad1)") (class "Default")
      (node (ref "C28") (pin "1") (pinfunction "1_1") (pintype "passive"))
      (node (ref "R40") (pin "1") (pinfunction "1_1") (pintype "passive"))
      (node (ref "R42") (pin "1") (pinfunction "1_1") (pintype "passive"))
    )
    (net (code "30") (name "Net-(C29-Pad1)") (class "Default")
      (node (ref "C29") (pin "1") (pinfunction "1_1") (pintype "passive"))
      (node (ref "R39") (pin "1") (pinfunction "1_1") (pintype "passive"))
      (node (ref "R41") (pin "1") (pinfunction "1_1") (pintype "passive"))
    )
    (net (code "31") (name "Net-(C30-Pad1)") (class "Default")
      (node (ref "C30") (pin "1") (pinfunction "1_1") (pintype "passive"))
      (node (ref "R13") (pin "1") (pinfunction "1_1") (pintype "passive"))
      (node (ref "R38") (pin "1") (pinfunction "1_1") (pintype "passive"))
    )
    (net (code "32") (name "Net-(C31-Pad1)") (class "Default")
      (node (ref "C31") (pin "1") (pinfunction "1_1") (pintype "passive"))
      (node (ref "C7") (pin "2") (pinfunction "2_2") (pintype "passive"))
      (node (ref "R51") (pin "1") (pinfunction "1_1") (pintype "passive"))
    )
    (net (code "33") (name "Net-(C32-Pad1)") (class "Default")
      (node (ref "C32") (pin "1") (pinfunction "1_1") (pintype "passive"))
      (node (ref "C8") (pin "2") (pinfunction "2_2") (pintype "passive"))
      (node (ref "R50") (pin "1") (pinfunction "1_1") (pintype "passive"))
    )
    (net (code "34") (name "Net-(C33-Pad1)") (class "Default")
      (node (ref "C33") (pin "1") (pinfunction "1_1") (pintype "passive"))
      (node (ref "C9") (pin "2") (pinfunction "2_2") (pintype "passive"))
      (node (ref "R49") (pin "1") (pinfunction "1_1") (pintype "passive"))
    )
    (net (code "35") (name "Net-(C34-Pad+)") (class "Default")
      (node (ref "C34") (pin "+") (pinfunction "+_+") (pintype "passive"))
      (node (ref "R54") (pin "2") (pinfunction "2_2") (pintype "passive"))
      (node (ref "R56") (pin "2") (pinfunction "2_2") (pintype "passive"))
    )
    (net (code "36") (name "Net-(C35-Pad-)") (class "Default")
      (node (ref "C35") (pin "-") (pinfunction "-_-") (pintype "passive"))
      (node (ref "R55") (pin "2") (pinfunction "2_2") (pintype "passive"))
      (node (ref "R57") (pin "2") (pinfunction "2_2") (pintype "passive"))
    )
    (net (code "37") (name "Net-(C40-Pad+)") (class "Default")
      (node (ref "C40") (pin "+") (pinfunction "+_+") (pintype "passive"))
      (node (ref "R94") (pin "2") (pinfunction "2_2") (pintype "passive"))
    )
    (net (code "38") (name "Net-(C41-Pad+)") (class "Default")
      (node (ref "C41") (pin "+") (pinfunction "+_+") (pintype "passive"))
      (node (ref "R86") (pin "2") (pinfunction "2_2") (pintype "passive"))
      (node (ref "R89") (pin "1") (pinfunction "1_1") (pintype "passive"))
    )
    (net (code "39") (name "Net-(C42-Pad+)") (class "Default")
      (node (ref "C42") (pin "+") (pinfunction "+_+") (pintype "passive"))
      (node (ref "R85") (pin "2") (pinfunction "2_2") (pintype "passive"))
      (node (ref "R88") (pin "1") (pinfunction "1_1") (pintype "passive"))
    )
    (net (code "40") (name "Net-(D2-PadC)") (class "Default")
      (node (ref "D2") (pin "C") (pinfunction "C_C") (pintype "passive"))
      (node (ref "Q2") (pin "C") (pinfunction "C_C") (pintype "passive"))
      (node (ref "R61") (pin "1") (pinfunction "1_1") (pintype "passive"))
      (node (ref "R68") (pin "2") (pinfunction "2_2") (pintype "passive"))
      (node (ref "R72") (pin "2") (pinfunction "2_2") (pintype "passive"))
    )
    (net (code "41") (name "Net-(IC1-1A)") (class "Default")
      (node (ref "IC1") (pin "2") (pinfunction "1A_2") (pintype "input"))
      (node (ref "R53") (pin "1") (pinfunction "1_1") (pintype "passive"))
    )
    (net (code "42") (name "Net-(IC1-2A)") (class "Default")
      (node (ref "IC1") (pin "7") (pinfunction "2A_7") (pintype "input"))
      (node (ref "R3") (pin "2") (pinfunction "2_2") (pintype "passive"))
    )
    (net (code "43") (name "Net-(IC1-3A)") (class "Default")
      (node (ref "IC1") (pin "10") (pinfunction "3A_10") (pintype "input"))
      (node (ref "R2") (pin "2") (pinfunction "2_2") (pintype "passive"))
    )
    (net (code "44") (name "Net-(IC1-4A)") (class "Default")
      (node (ref "IC1") (pin "15") (pinfunction "4A_15") (pintype "input"))
      (node (ref "R52") (pin "2") (pinfunction "2_2") (pintype "passive"))
    )
    (net (code "45") (name "Net-(IC1-4Y)") (class "Default")
      (node (ref "IC1") (pin "14") (pinfunction "4Y_14") (pintype "output"))
      (node (ref "R1") (pin "2") (pinfunction "2_2") (pintype "passive"))
    )
    (net (code "46") (name "Net-(IC2A-+IN)") (class "Default")
      (node (ref "C17") (pin "2") (pinfunction "2_2") (pintype "passive"))
      (node (ref "IC2") (pin "3") (pinfunction "+IN_3") (pintype "input"))
      (node (ref "R23") (pin "2") (pinfunction "2_2") (pintype "passive"))
    )
    (net (code "47") (name "Net-(IC2A--IN)") (class "Default")
      (node (ref "IC2") (pin "1") (pinfunction "OUT_1") (pintype "output"))
      (node (ref "IC2") (pin "2") (pinfunction "-IN_2") (pintype "input"))
      (node (ref "R24") (pin "2") (pinfunction "2_2") (pintype "passive"))
    )
    (net (code "48") (name "Net-(IC2B-+IN)") (class "Default")
      (node (ref "IC2") (pin "5") (pinfunction "+IN_5") (pintype "input"))
      (node (ref "R25") (pin "1") (pinfunction "1_1") (pintype "passive"))
      (node (ref "R29") (pin "1") (pinfunction "1_1") (pintype "passive"))
    )
    (net (code "49") (name "Net-(IC2B--IN)") (class "Default")
      (node (ref "IC2") (pin "6") (pinfunction "-IN_6") (pintype "input"))
      (node (ref "R26") (pin "1") (pinfunction "1_1") (pintype "passive"))
      (node (ref "R28") (pin "2") (pinfunction "2_2") (pintype "passive"))
    )
    (net (code "50") (name "Net-(IC2B-OUT)") (class "Default")
      (node (ref "IC2") (pin "7") (pinfunction "OUT_7") (pintype "output"))
      (node (ref "R28") (pin "1") (pinfunction "1_1") (pintype "passive"))
      (node (ref "R32") (pin "2") (pinfunction "2_2") (pintype "passive"))
    )
    (net (code "51") (name "Net-(IC2C-V+)") (class "Default")
      (node (ref "C12") (pin "2") (pinfunction "2_2") (pintype "passive"))
      (node (ref "C14") (pin "2") (pinfunction "2_2") (pintype "passive"))
      (node (ref "C19") (pin "2") (pinfunction "2_2") (pintype "passive"))
      (node (ref "C22") (pin "2") (pinfunction "2_2") (pintype "passive"))
      (node (ref "C23") (pin "2") (pinfunction "2_2") (pintype "passive"))
      (node (ref "C24") (pin "2") (pinfunction "2_2") (pintype "passive"))
      (node (ref "IC2") (pin "8") (pinfunction "V+_8") (pintype "power_in"))
      (node (ref "IC3") (pin "8") (pinfunction "V+_8") (pintype "power_in"))
      (node (ref "IC4") (pin "8") (pinfunction "V+_8") (pintype "power_in"))
      (node (ref "IC5") (pin "8") (pinfunction "V+_8") (pintype "power_in"))
      (node (ref "IC6") (pin "8") (pinfunction "V+_8") (pintype "power_in"))
      (node (ref "IC7") (pin "8") (pinfunction "V+_8") (pintype "power_in"))
      (node (ref "R54") (pin "1") (pinfunction "1_1") (pintype "passive"))
    )
    (net (code "52") (name "Net-(IC2C-V-)") (class "Default")
      (node (ref "C13") (pin "1") (pinfunction "1_1") (pintype "passive"))
      (node (ref "C15") (pin "1") (pinfunction "1_1") (pintype "passive"))
      (node (ref "C20") (pin "1") (pinfunction "1_1") (pintype "passive"))
      (node (ref "C25") (pin "1") (pinfunction "1_1") (pintype "passive"))
      (node (ref "C26") (pin "1") (pinfunction "1_1") (pintype "passive"))
      (node (ref "C27") (pin "1") (pinfunction "1_1") (pintype "passive"))
      (node (ref "IC2") (pin "4") (pinfunction "V-_4") (pintype "power_in"))
      (node (ref "IC3") (pin "4") (pinfunction "V-_4") (pintype "power_in"))
      (node (ref "IC4") (pin "4") (pinfunction "V-_4") (pintype "power_in"))
      (node (ref "IC5") (pin "4") (pinfunction "V-_4") (pintype "power_in"))
      (node (ref "IC6") (pin "4") (pinfunction "V-_4") (pintype "power_in"))
      (node (ref "IC7") (pin "4") (pinfunction "V-_4") (pintype "power_in"))
      (node (ref "R55") (pin "1") (pinfunction "1_1") (pintype "passive"))
    )
    (net (code "53") (name "Net-(IC3A-+IN)") (class "Default")
      (node (ref "C16") (pin "2") (pinfunction "2_2") (pintype "passive"))
      (node (ref "IC3") (pin "3") (pinfunction "+IN_3") (pintype "input"))
      (node (ref "R21") (pin "2") (pinfunction "2_2") (pintype "passive"))
    )
    (net (code "54") (name "Net-(IC3A--IN)") (class "Default")
      (node (ref "IC3") (pin "1") (pinfunction "OUT_1") (pintype "output"))
      (node (ref "IC3") (pin "2") (pinfunction "-IN_2") (pintype "input"))
      (node (ref "R17") (pin "1") (pinfunction "1_1") (pintype "passive"))
    )
    (net (code "55") (name "Net-(IC3B-+IN)") (class "Default")
      (node (ref "IC3") (pin "5") (pinfunction "+IN_5") (pintype "input"))
      (node (ref "R30") (pin "2") (pinfunction "2_2") (pintype "passive"))
      (node (ref "U$1") (pin "P$3") (pinfunction "E_P$3") (pintype "passive"))
      (node (ref "U$2") (pin "P$3") (pinfunction "E_P$3") (pintype "passive"))
      (node (ref "U$3") (pin "P$3") (pinfunction "E_P$3") (pintype "passive"))
      (node (ref "U$4") (pin "P$3") (pinfunction "E_P$3") (pintype "passive"))
      (node (ref "U$5") (pin "P$3") (pinfunction "E_P$3") (pintype "passive"))
    )
    (net (code "56") (name "Net-(IC3B--IN)") (class "Default")
      (node (ref "IC3") (pin "6") (pinfunction "-IN_6") (pintype "input"))
      (node (ref "R10") (pin "1") (pinfunction "1_1") (pintype "passive"))
      (node (ref "R11") (pin "1") (pinfunction "1_1") (pintype "passive"))
      (node (ref "R12") (pin "1") (pinfunction "1_1") (pintype "passive"))
      (node (ref "R27") (pin "2") (pinfunction "2_2") (pintype "passive"))
      (node (ref "R9") (pin "1") (pinfunction "1_1") (pintype "passive"))
      (node (ref "U$1") (pin "P$1") (pinfunction "A_P$1") (pintype "passive"))
    )
    (net (code "57") (name "Net-(IC3B-OUT)") (class "Default")
      (node (ref "IC3") (pin "7") (pinfunction "OUT_7") (pintype "output"))
      (node (ref "R27") (pin "1") (pinfunction "1_1") (pintype "passive"))
      (node (ref "R31") (pin "2") (pinfunction "2_2") (pintype "passive"))
    )
    (net (code "58") (name "Net-(IC4A-+IN)") (class "Default")
      (node (ref "C18") (pin "2") (pinfunction "2_2") (pintype "passive"))
      (node (ref "IC4") (pin "3") (pinfunction "+IN_3") (pintype "input"))
      (node (ref "R35") (pin "1") (pinfunction "1_1") (pintype "passive"))
    )
    (net (code "59") (name "Net-(IC4A--IN)") (class "Default")
      (node (ref "IC4") (pin "1") (pinfunction "OUT_1") (pintype "output"))
      (node (ref "IC4") (pin "2") (pinfunction "-IN_2") (pintype "input"))
      (node (ref "R34") (pin "2") (pinfunction "2_2") (pintype "passive"))
    )
    (net (code "60") (name "Net-(IC4B-+IN)") (class "Default")
      (node (ref "C21") (pin "1") (pinfunction "1_1") (pintype "passive"))
      (node (ref "IC4") (pin "5") (pinfunction "+IN_5") (pintype "input"))
      (node (ref "R36") (pin "2") (pinfunction "2_2") (pintype "passive"))
    )
    (net (code "61") (name "Net-(IC4B--IN)") (class "Default")
      (node (ref "IC4") (pin "6") (pinfunction "-IN_6") (pintype "input"))
      (node (ref "IC4") (pin "7") (pinfunction "OUT_7") (pintype "output"))
      (node (ref "R37") (pin "2") (pinfunction "2_2") (pintype "passive"))
    )
    (net (code "62") (name "Net-(IC5A-+IN)") (class "Default")
      (node (ref "C33") (pin "2") (pinfunction "2_2") (pintype "passive"))
      (node (ref "IC5") (pin "3") (pinfunction "+IN_3") (pintype "input"))
      (node (ref "R46") (pin "2") (pinfunction "2_2") (pintype "passive"))
    )
    (net (code "63") (name "Net-(IC5A--IN)") (class "Default")
      (node (ref "IC5") (pin "1") (pinfunction "OUT_1") (pintype "output"))
      (node (ref "IC5") (pin "2") (pinfunction "-IN_2") (pintype "input"))
      (node (ref "R49") (pin "2") (pinfunction "2_2") (pintype "passive"))
    )
    (net (code "64") (name "Net-(IC5B-+IN)") (class "Default")
      (node (ref "C30") (pin "2") (pinfunction "2_2") (pintype "passive"))
      (node (ref "IC5") (pin "5") (pinfunction "+IN_5") (pintype "input"))
      (node (ref "R43") (pin "2") (pinfunction "2_2") (pintype "passive"))
    )
    (net (code "65") (name "Net-(IC5B--IN)") (class "Default")
      (node (ref "IC5") (pin "6") (pinfunction "-IN_6") (pintype "input"))
      (node (ref "IC5") (pin "7") (pinfunction "OUT_7") (pintype "output"))
      (node (ref "R13") (pin "2") (pinfunction "2_2") (pintype "passive"))
    )
    (net (code "66") (name "Net-(IC6A-+IN)") (class "Default")
      (node (ref "C32") (pin "2") (pinfunction "2_2") (pintype "passive"))
      (node (ref "IC6") (pin "3") (pinfunction "+IN_3") (pintype "input"))
      (node (ref "R47") (pin "2") (pinfunction "2_2") (pintype "passive"))
    )
    (net (code "67") (name "Net-(IC6A--IN)") (class "Default")
      (node (ref "IC6") (pin "1") (pinfunction "OUT_1") (pintype "output"))
      (node (ref "IC6") (pin "2") (pinfunction "-IN_2") (pintype "input"))
      (node (ref "R50") (pin "2") (pinfunction "2_2") (pintype "passive"))
    )
    (net (code "68") (name "Net-(IC6B-+IN)") (class "Default")
      (node (ref "C29") (pin "2") (pinfunction "2_2") (pintype "passive"))
      (node (ref "IC6") (pin "5") (pinfunction "+IN_5") (pintype "input"))
      (node (ref "R44") (pin "2") (pinfunction "2_2") (pintype "passive"))
    )
    (net (code "69") (name "Net-(IC6B--IN)") (class "Default")
      (node (ref "IC6") (pin "6") (pinfunction "-IN_6") (pintype "input"))
      (node (ref "IC6") (pin "7") (pinfunction "OUT_7") (pintype "output"))
      (node (ref "R41") (pin "2") (pinfunction "2_2") (pintype "passive"))
    )
    (net (code "70") (name "Net-(IC7A-+IN)") (class "Default")
      (node (ref "C31") (pin "2") (pinfunction "2_2") (pintype "passive"))
      (node (ref "IC7") (pin "3") (pinfunction "+IN_3") (pintype "input"))
      (node (ref "R48") (pin "2") (pinfunction "2_2") (pintype "passive"))
    )
    (net (code "71") (name "Net-(IC7A--IN)") (class "Default")
      (node (ref "IC7") (pin "1") (pinfunction "OUT_1") (pintype "output"))
      (node (ref "IC7") (pin "2") (pinfunction "-IN_2") (pintype "input"))
      (node (ref "R51") (pin "2") (pinfunction "2_2") (pintype "passive"))
    )
    (net (code "72") (name "Net-(IC7B-+IN)") (class "Default")
      (node (ref "C28") (pin "2") (pinfunction "2_2") (pintype "passive"))
      (node (ref "IC7") (pin "5") (pinfunction "+IN_5") (pintype "input"))
      (node (ref "R45") (pin "2") (pinfunction "2_2") (pintype "passive"))
    )
    (net (code "73") (name "Net-(IC7B--IN)") (class "Default")
      (node (ref "IC7") (pin "6") (pinfunction "-IN_6") (pintype "input"))
      (node (ref "IC7") (pin "7") (pinfunction "OUT_7") (pintype "output"))
      (node (ref "R42") (pin "2") (pinfunction "2_2") (pintype "passive"))
    )
    (net (code "74") (name "Net-(IC8A-+IN)") (class "Default")
      (node (ref "IC8") (pin "3") (pinfunction "+IN_3") (pintype "input"))
      (node (ref "R77") (pin "1") (pinfunction "1_1") (pintype "passive"))
    )
    (net (code "75") (name "Net-(IC8A--IN)") (class "Default")
      (node (ref "IC8") (pin "2") (pinfunction "-IN_2") (pintype "input"))
      (node (ref "R81") (pin "1") (pinfunction "1_1") (pintype "passive"))
      (node (ref "R82") (pin "1") (pinfunction "1_1") (pintype "passive"))
    )
    (net (code "76") (name "Net-(IC8A-OUT)") (class "Default")
      (node (ref "IC8") (pin "1") (pinfunction "OUT_1") (pintype "output"))
      (node (ref "R82") (pin "2") (pinfunction "2_2") (pintype "passive"))
      (node (ref "R85") (pin "1") (pinfunction "1_1") (pintype "passive"))
    )
    (net (code "77") (name "Net-(IC8B-+IN)") (class "Default")
      (node (ref "IC8") (pin "5") (pinfunction "+IN_5") (pintype "input"))
      (node (ref "R91") (pin "1") (pinfunction "1_1") (pintype "passive"))
    )
    (net (code "78") (name "Net-(IC8B--IN)") (class "Default")
      (node (ref "IC8") (pin "6") (pinfunction "-IN_6") (pintype "input"))
      (node (ref "IC8") (pin "7") (pinfunction "OUT_7") (pintype "output"))
      (node (ref "R94") (pin "1") (pinfunction "1_1") (pintype "passive"))
    )
    (net (code "79") (name "Net-(IC8C-V+)") (class "Default")
      (node (ref "C38") (pin "2") (pinfunction "2_2") (pintype "passive"))
      (node (ref "C39") (pin "2") (pinfunction "2_2") (pintype "passive"))
      (node (ref "IC8") (pin "8") (pinfunction "V+_8") (pintype "power_in"))
      (node (ref "IC9") (pin "8") (pinfunction "V+_8") (pintype "power_in"))
    )
    (net (code "80") (name "Net-(IC8C-V-)") (class "Default")
      (node (ref "C36") (pin "1") (pinfunction "1_1") (pintype "passive"))
      (node (ref "C37") (pin "1") (pinfunction "1_1") (pintype "passive"))
      (node (ref "IC8") (pin "4") (pinfunction "V-_4") (pintype "power_in"))
      (node (ref "IC9") (pin "4") (pinfunction "V-_4") (pintype "power_in"))
    )
    (net (code "81") (name "Net-(IC9A-+IN)") (class "Default")
      (node (ref "IC9") (pin "3") (pinfunction "+IN_3") (pintype "input"))
      (node (ref "R78") (pin "1") (pinfunction "1_1") (pintype "passive"))
    )
    (net (code "82") (name "Net-(IC9A--IN)") (class "Default")
      (node (ref "IC9") (pin "2") (pinfunction "-IN_2") (pintype "input"))
      (node (ref "R83") (pin "1") (pinfunction "1_1") (pintype "passive"))
      (node (ref "R84") (pin "2") (pinfunction "2_2") (pintype "passive"))
    )
    (net (code "83") (name "Net-(IC9A-OUT)") (class "Default")
      (node (ref "IC9") (pin "1") (pinfunction "OUT_1") (pintype "output"))
      (node (ref "R83") (pin "2") (pinfunction "2_2") (pintype "passive"))
      (node (ref "R86") (pin "1") (pinfunction "1_1") (pintype "passive"))
    )
    (net (code "84") (name "Net-(IC9B-+IN)") (class "Default")
      (node (ref "IC9") (pin "5") (pinfunction "+IN_5") (pintype "input"))
      (node (ref "R95") (pin "1") (pinfunction "1_1") (pintype "passive"))
    )
    (net (code "85") (name "Net-(IC9B--IN)") (class "Default")
      (node (ref "IC9") (pin "6") (pinfunction "-IN_6") (pintype "input"))
      (node (ref "R88") (pin "2") (pinfunction "2_2") (pintype "passive"))
      (node (ref "R89") (pin "2") (pinfunction "2_2") (pintype "passive"))
      (node (ref "R90") (pin "1") (pinfunction "1_1") (pintype "passive"))
    )
    (net (code "86") (name "Net-(IC9B-OUT)") (class "Default")
      (node (ref "IC9") (pin "7") (pinfunction "OUT_7") (pintype "output"))
      (node (ref "R90") (pin "2") (pinfunction "2_2") (pintype "passive"))
      (node (ref "R93") (pin "1") (pinfunction "1_1") (pintype "passive"))
    )
    (net (code "87") (name "Net-(K1A-O)") (class "Default")
      (node (ref "K1") (pin "3") (pinfunction "O_3") (pintype "passive"))
      (node (ref "R32") (pin "1") (pinfunction "1_1") (pintype "passive"))
    )
    (net (code "88") (name "Net-(K1A-S)") (class "Default")
      (node (ref "K1") (pin "5") (pinfunction "S_5") (pintype "passive"))
      (node (ref "R29") (pin "2") (pinfunction "2_2") (pintype "passive"))
      (node (ref "R59") (pin "2") (pinfunction "2_2") (pintype "passive"))
      (node (ref "R63") (pin "2") (pinfunction "2_2") (pintype "passive"))
    )
    (net (code "89") (name "Net-(K1B-O)") (class "Default")
      (node (ref "K1") (pin "10") (pinfunction "O_10") (pintype "passive"))
      (node (ref "R31") (pin "1") (pinfunction "1_1") (pintype "passive"))
    )
    (net (code "90") (name "Net-(K1B-S)") (class "Default")
      (node (ref "K1") (pin "8") (pinfunction "S_8") (pintype "passive"))
      (node (ref "R30") (pin "1") (pinfunction "1_1") (pintype "passive"))
      (node (ref "R58") (pin "2") (pinfunction "2_2") (pintype "passive"))
      (node (ref "R60") (pin "2") (pinfunction "2_2") (pintype "passive"))
    )
    (net (code "91") (name "Net-(K1C-+)") (class "Default")
      (node (ref "D1") (pin "C") (pinfunction "C_C") (pintype "passive"))
      (node (ref "K1") (pin "1") (pinfunction "+_1") (pintype "passive"))
      (node (ref "R61") (pin "2") (pinfunction "2_2") (pintype "passive"))
      (node (ref "R62") (pin "2") (pinfunction "2_2") (pintype "passive"))
      (node (ref "R74") (pin "1") (pinfunction "1_1") (pintype "passive"))
    )
    (net (code "92") (name "Net-(K1C--)") (class "Default")
      (node (ref "D1") (pin "A") (pinfunction "A_A") (pintype "passive"))
      (node (ref "K1") (pin "12") (pinfunction "-_12") (pintype "passive"))
      (node (ref "Q1") (pin "C") (pinfunction "C_C") (pintype "passive"))
    )
    (net (code "93") (name "Net-(K2B-O)") (class "Default")
      (node (ref "K2") (pin "10") (pinfunction "O_10") (pintype "passive"))
      (node (ref "R87") (pin "2") (pinfunction "2_2") (pintype "passive"))
    )
    (net (code "94") (name "Net-(K2C-+)") (class "Default")
      (node (ref "D3") (pin "C") (pinfunction "C_C") (pintype "passive"))
      (node (ref "K2") (pin "1") (pinfunction "+_1") (pintype "passive"))
      (node (ref "R74") (pin "2") (pinfunction "2_2") (pintype "passive"))
    )
    (net (code "95") (name "Net-(K2C--)") (class "Default")
      (node (ref "D3") (pin "A") (pinfunction "A_A") (pintype "passive"))
      (node (ref "K2") (pin "12") (pinfunction "-_12") (pintype "passive"))
      (node (ref "Q3") (pin "C") (pinfunction "C_C") (pintype "passive"))
    )
    (net (code "96") (name "Net-(Q1-PadB)") (class "Default")
      (node (ref "Q1") (pin "B") (pinfunction "B_B") (pintype "passive"))
      (node (ref "R70") (pin "1") (pinfunction "1_1") (pintype "passive"))
    )
    (net (code "97") (name "Net-(Q2-PadB)") (class "Default")
      (node (ref "Q2") (pin "B") (pinfunction "B_B") (pintype "passive"))
      (node (ref "R75") (pin "1") (pinfunction "1_1") (pintype "passive"))
    )
    (net (code "98") (name "Net-(Q3-PadB)") (class "Default")
      (node (ref "Q3") (pin "B") (pinfunction "B_B") (pintype "passive"))
      (node (ref "R68") (pin "1") (pinfunction "1_1") (pintype "passive"))
    )
    (net (code "99") (name "Net-(R26-Pad2)") (class "Default")
      (node (ref "R26") (pin "2") (pinfunction "2_2") (pintype "passive"))
      (node (ref "R4") (pin "1") (pinfunction "1_1") (pintype "passive"))
      (node (ref "R5") (pin "1") (pinfunction "1_1") (pintype "passive"))
      (node (ref "R6") (pin "1") (pinfunction "1_1") (pintype "passive"))
      (node (ref "R7") (pin "1") (pinfunction "1_1") (pintype "passive"))
      (node (ref "R8") (pin "1") (pinfunction "1_1") (pintype "passive"))
    )
    (net (code "100") (name "Net-(R77-Pad2)") (class "Default")
      (node (ref "R77") (pin "2") (pinfunction "2_2") (pintype "passive"))
      (node (ref "R80") (pin "1") (pinfunction "1_1") (pintype "passive"))
    )
    (net (code "101") (name "Net-(R78-Pad2)") (class "Default")
      (node (ref "R78") (pin "2") (pinfunction "2_2") (pintype "passive"))
      (node (ref "R79") (pin "1") (pinfunction "1_1") (pintype "passive"))
    )
    (net (code "102") (name "Net-(R91-Pad2)") (class "Default")
      (node (ref "R91") (pin "2") (pinfunction "2_2") (pintype "passive"))
      (node (ref "R92") (pin "1") (pinfunction "1_1") (pintype "passive"))
    )
    (net (code "103") (name "Net-(U$1-A1)") (class "Default")
      (node (ref "R22") (pin "2") (pinfunction "2_2") (pintype "passive"))
      (node (ref "U$1") (pin "P$2") (pinfunction "A1_P$2") (pintype "passive"))
    )
    (net (code "104") (name "Net-(U$1-E1)") (class "Default")
      (node (ref "R25") (pin "2") (pinfunction "2_2") (pintype "passive"))
      (node (ref "U$1") (pin "P$4") (pinfunction "E1_P$4") (pintype "passive"))
      (node (ref "U$2") (pin "P$4") (pinfunction "E1_P$4") (pintype "passive"))
      (node (ref "U$3") (pin "P$4") (pinfunction "E1_P$4") (pintype "passive"))
      (node (ref "U$4") (pin "P$4") (pinfunction "E1_P$4") (pintype "passive"))
      (node (ref "U$5") (pin "P$4") (pinfunction "E1_P$4") (pintype "passive"))
    )
    (net (code "105") (name "Net-(U$1-S)") (class "Default")
      (node (ref "C7") (pin "1") (pinfunction "1_1") (pintype "passive"))
      (node (ref "U$1") (pin "P$5") (pinfunction "S_P$5") (pintype "passive"))
    )
    (net (code "106") (name "Net-(U$1-S1)") (class "Default")
      (node (ref "R8") (pin "2") (pinfunction "2_2") (pintype "passive"))
      (node (ref "U$1") (pin "P$6") (pinfunction "S1_P$6") (pintype "passive"))
    )
    (net (code "107") (name "Net-(U$2-A)") (class "Default")
      (node (ref "R10") (pin "2") (pinfunction "2_2") (pintype "passive"))
      (node (ref "U$2") (pin "P$1") (pinfunction "A_P$1") (pintype "passive"))
    )
    (net (code "108") (name "Net-(U$2-A1)") (class "Default")
      (node (ref "R20") (pin "2") (pinfunction "2_2") (pintype "passive"))
      (node (ref "U$2") (pin "P$2") (pinfunction "A1_P$2") (pintype "passive"))
    )
    (net (code "109") (name "Net-(U$2-S)") (class "Default")
      (node (ref "R16") (pin "2") (pinfunction "2_2") (pintype "passive"))
      (node (ref "U$2") (pin "P$5") (pinfunction "S_P$5") (pintype "passive"))
    )
    (net (code "110") (name "Net-(U$2-S1)") (class "Default")
      (node (ref "R4") (pin "2") (pinfunction "2_2") (pintype "passive"))
      (node (ref "U$2") (pin "P$6") (pinfunction "S1_P$6") (pintype "passive"))
    )
    (net (code "111") (name "Net-(U$3-A)") (class "Default")
      (node (ref "R11") (pin "2") (pinfunction "2_2") (pintype "passive"))
      (node (ref "U$3") (pin "P$1") (pinfunction "A_P$1") (pintype "passive"))
    )
    (net (code "112") (name "Net-(U$3-A1)") (class "Default")
      (node (ref "C3") (pin "1") (pinfunction "1_1") (pintype "passive"))
      (node (ref "U$3") (pin "P$2") (pinfunction "A1_P$2") (pintype "passive"))
    )
    (net (code "113") (name "Net-(U$3-S)") (class "Default")
      (node (ref "C11") (pin "1") (pinfunction "1_1") (pintype "passive"))
      (node (ref "U$3") (pin "P$5") (pinfunction "S_P$5") (pintype "passive"))
    )
    (net (code "114") (name "Net-(U$3-S1)") (class "Default")
      (node (ref "R5") (pin "2") (pinfunction "2_2") (pintype "passive"))
      (node (ref "U$3") (pin "P$6") (pinfunction "S1_P$6") (pintype "passive"))
    )
    (net (code "115") (name "Net-(U$4-A)") (class "Default")
      (node (ref "R9") (pin "2") (pinfunction "2_2") (pintype "passive"))
      (node (ref "U$4") (pin "P$1") (pinfunction "A_P$1") (pintype "passive"))
    )
    (net (code "116") (name "Net-(U$4-A1)") (class "Default")
      (node (ref "R19") (pin "2") (pinfunction "2_2") (pintype "passive"))
      (node (ref "U$4") (pin "P$2") (pinfunction "A1_P$2") (pintype "passive"))
    )
    (net (code "117") (name "Net-(U$4-S)") (class "Default")
      (node (ref "R15") (pin "2") (pinfunction "2_2") (pintype "passive"))
      (node (ref "U$4") (pin "P$5") (pinfunction "S_P$5") (pintype "passive"))
    )
    (net (code "118") (name "Net-(U$4-S1)") (class "Default")
      (node (ref "R6") (pin "2") (pinfunction "2_2") (pintype "passive"))
      (node (ref "U$4") (pin "P$6") (pinfunction "S1_P$6") (pintype "passive"))
    )
    (net (code "119") (name "Net-(U$5-A)") (class "Default")
      (node (ref "R12") (pin "2") (pinfunction "2_2") (pintype "passive"))
      (node (ref "U$5") (pin "P$1") (pinfunction "A_P$1") (pintype "passive"))
    )
    (net (code "120") (name "Net-(U$5-A1)") (class "Default")
      (node (ref "R18") (pin "2") (pinfunction "2_2") (pintype "passive"))
      (node (ref "U$5") (pin "P$2") (pinfunction "A1_P$2") (pintype "passive"))
    )
    (net (code "121") (name "Net-(U$5-S)") (class "Default")
      (node (ref "R14") (pin "2") (pinfunction "2_2") (pintype "passive"))
      (node (ref "U$5") (pin "P$5") (pinfunction "S_P$5") (pintype "passive"))
    )
    (net (code "122") (name "Net-(U$5-S1)") (class "Default")
      (node (ref "R7") (pin "2") (pinfunction "2_2") (pintype "passive"))
      (node (ref "U$5") (pin "P$6") (pinfunction "S1_P$6") (pintype "passive"))
    )
    (net (code "123") (name "Net-(X1B-S)") (class "Default")
      (node (ref "X1") (pin "2") (pinfunction "S_2") (pintype "passive"))
      (node (ref "X2") (pin "3") (pinfunction "S_3") (pintype "passive"))
    )
    (net (code "124") (name "Net-(X1G-S)") (class "Default")
      (node (ref "X1") (pin "7") (pinfunction "S_7") (pintype "passive"))
      (node (ref "X2") (pin "2") (pinfunction "S_2") (pintype "passive"))
    )
    (net (code "125") (name "Net-(X3B-S)") (class "Default")
      (node (ref "X3") (pin "2") (pinfunction "S_2") (pintype "passive"))
      (node (ref "X4") (pin "5") (pinfunction "S_5") (pintype "passive"))
    )
    (net (code "126") (name "Net-(X3C-S)") (class "Default")
      (node (ref "X3") (pin "3") (pinfunction "S_3") (pintype "passive"))
      (node (ref "X4") (pin "4") (pinfunction "S_4") (pintype "passive"))
    )
    (net (code "127") (name "Net-(X3D-S)") (class "Default")
      (node (ref "X3") (pin "4") (pinfunction "S_4") (pintype "passive"))
      (node (ref "X4") (pin "3") (pinfunction "S_3") (pintype "passive"))
    )
    (net (code "128") (name "Net-(X3G-S)") (class "Default")
      (node (ref "X3") (pin "7") (pinfunction "S_7") (pintype "passive"))
      (node (ref "X4") (pin "2") (pinfunction "S_2") (pintype "passive"))
    )
    (net (code "129") (name "Net-(X5A-S)") (class "Default")
      (node (ref "R3") (pin "1") (pinfunction "1_1") (pintype "passive"))
      (node (ref "R65") (pin "2") (pinfunction "2_2") (pintype "passive"))
      (node (ref "X5") (pin "1") (pinfunction "S_1") (pintype "passive"))
    )
    (net (code "130") (name "Net-(X5B-S)") (class "Default")
      (node (ref "R53") (pin "2") (pinfunction "2_2") (pintype "passive"))
      (node (ref "R67") (pin "2") (pinfunction "2_2") (pintype "passive"))
      (node (ref "X5") (pin "2") (pinfunction "S_2") (pintype "passive"))
    )
    (net (code "131") (name "Net-(X5C-S)") (class "Default")
      (node (ref "R2") (pin "1") (pinfunction "1_1") (pintype "passive"))
      (node (ref "R64") (pin "2") (pinfunction "2_2") (pintype "passive"))
      (node (ref "X5") (pin "3") (pinfunction "S_3") (pintype "passive"))
    )
    (net (code "132") (name "Net-(X5D-S)") (class "Default")
      (node (ref "R52") (pin "1") (pinfunction "1_1") (pintype "passive"))
      (node (ref "R66") (pin "2") (pinfunction "2_2") (pintype "passive"))
      (node (ref "X5") (pin "4") (pinfunction "S_4") (pintype "passive"))
    )
    (net (code "133") (name "Net-(X5E-S)") (class "Default")
      (node (ref "R70") (pin "2") (pinfunction "2_2") (pintype "passive"))
      (node (ref "R71") (pin "1") (pinfunction "1_1") (pintype "passive"))
      (node (ref "X5") (pin "5") (pinfunction "S_5") (pintype "passive"))
    )
    (net (code "134") (name "Net-(X5F-S)") (class "Default")
      (node (ref "R75") (pin "2") (pinfunction "2_2") (pintype "passive"))
      (node (ref "R76") (pin "1") (pinfunction "1_1") (pintype "passive"))
      (node (ref "X5") (pin "6") (pinfunction "S_6") (pintype "passive"))
    )
    (net (code "135") (name "Net-(X6B-S)") (class "Default")
      (node (ref "R72") (pin "1") (pinfunction "1_1") (pintype "passive"))
      (node (ref "X6") (pin "2") (pinfunction "S_2") (pintype "passive"))
    )
    (net (code "136") (name "Net-(X7A-S)") (class "Default")
      (node (ref "C40") (pin "-") (pinfunction "-_-") (pintype "passive"))
      (node (ref "R96") (pin "2") (pinfunction "2_2") (pintype "passive"))
      (node (ref "X7") (pin "1") (pinfunction "S_1") (pintype "passive"))
    )
    (net (code "137") (name "Net-(X7B-S)") (class "Default")
      (node (ref "C42") (pin "-") (pinfunction "-_-") (pintype "passive"))
      (node (ref "R98") (pin "2") (pinfunction "2_2") (pintype "passive"))
      (node (ref "X7") (pin "2") (pinfunction "S_2") (pintype "passive"))
    )
    (net (code "138") (name "Net-(X7E-S)") (class "Default")
      (node (ref "C41") (pin "-") (pinfunction "-_-") (pintype "passive"))
      (node (ref "R97") (pin "2") (pinfunction "2_2") (pintype "passive"))
      (node (ref "X7") (pin "5") (pinfunction "S_5") (pintype "passive"))
    )
    (net (code "139") (name "unconnected-(R93-Pad2)") (class "Default")
      (node (ref "R93") (pin "2") (pinfunction "2_2") (pintype "passive"))
    )
    (net (code "140") (name "unconnected-(X1A-S-Pad1)") (class "Default")
      (node (ref "X1") (pin "1") (pinfunction "S_1") (pintype "passive"))
    )
    (net (code "141") (name "unconnected-(X1H-S-Pad8)") (class "Default")
      (node (ref "X1") (pin "8") (pinfunction "S_8") (pintype "passive"))
    )
    (net (code "142") (name "unconnected-(X3A-S-Pad1)") (class "Default")
      (node (ref "X3") (pin "1") (pinfunction "S_1") (pintype "passive"))
    )
    (net (code "143") (name "unconnected-(X3H-S-Pad8)") (class "Default")
      (node (ref "X3") (pin "8") (pinfunction "S_8") (pintype "passive"))
    )
  )
)
